# hand_pcb.net
KiCad netlist of a schematic drawn in EAGLE
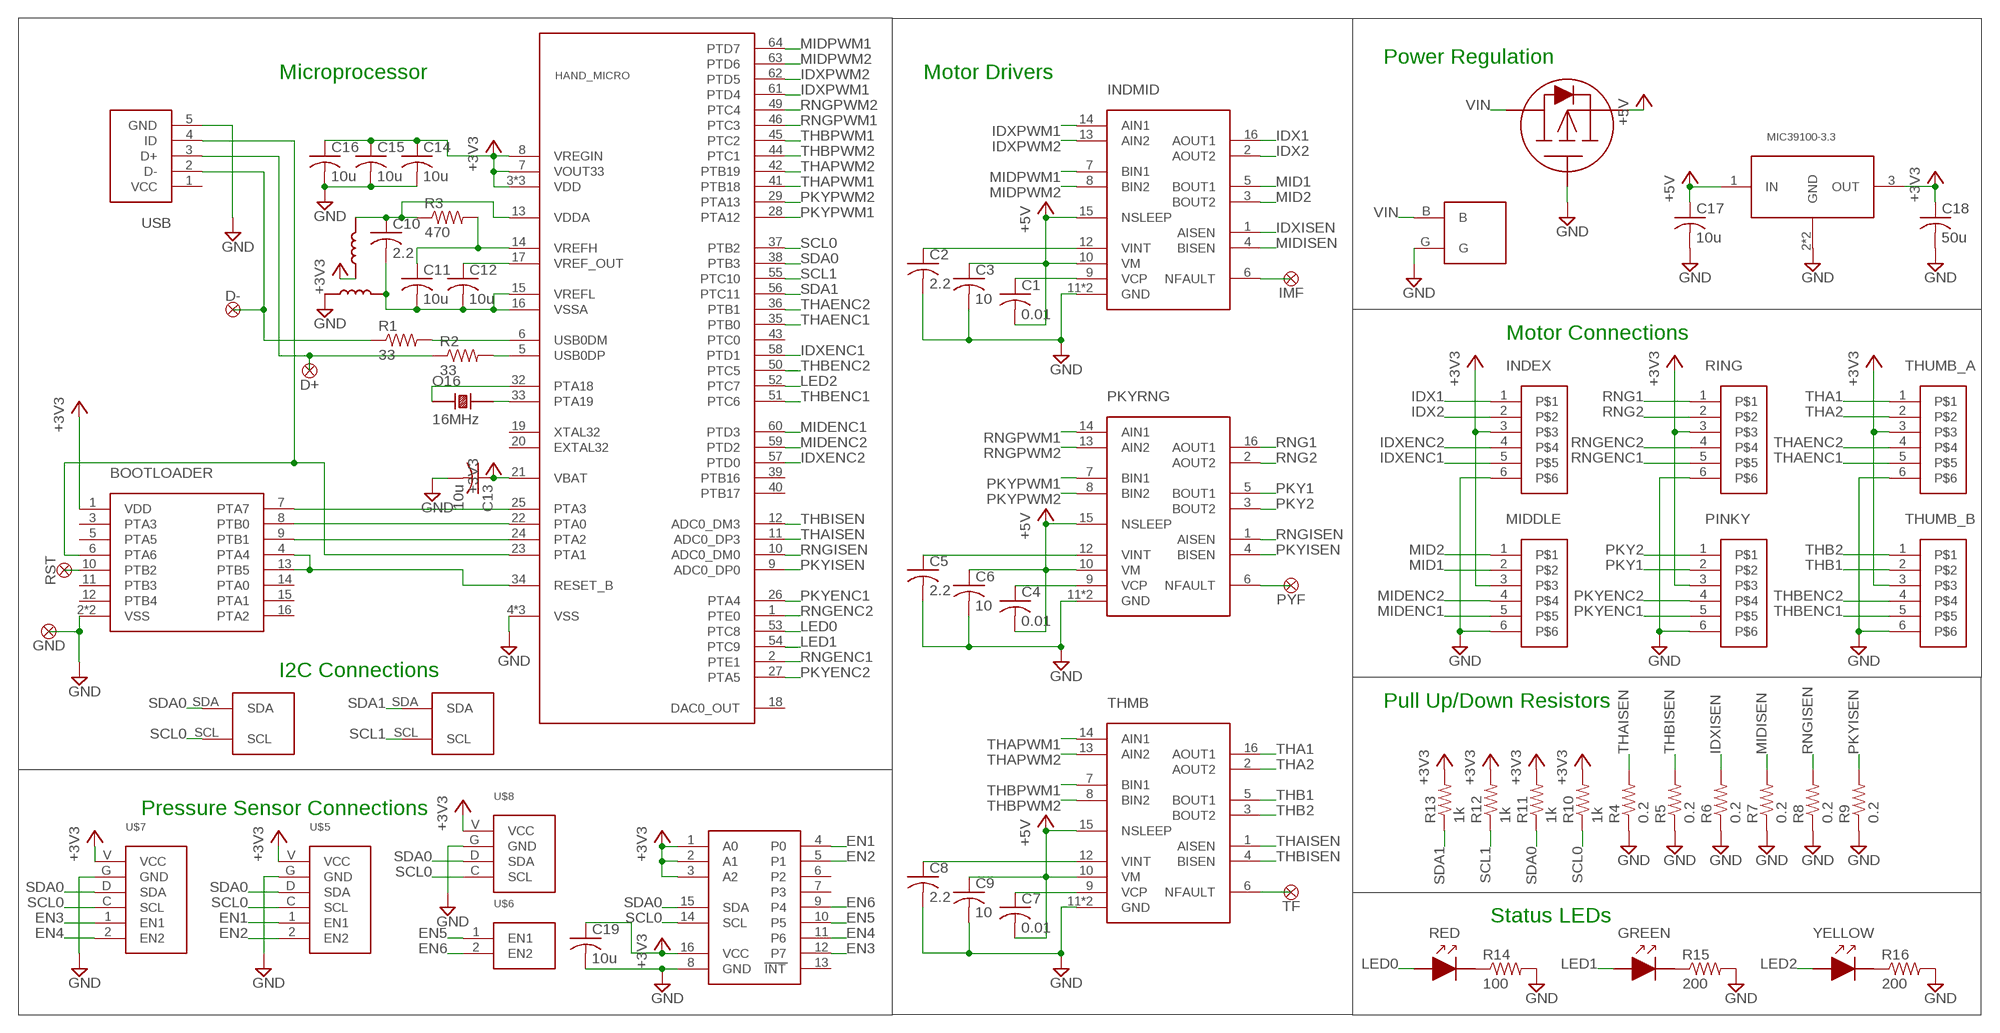
[diagram p0: schematic, sheet 1]

(export (version "E")
  (design (tool "Eeschema 10.0.6"))
  (components
    (comp (ref "BOOTLOADER")
      (value "MKL02Z32CORRECT")
      (footprint "eagle-import:QFN16")
      (libsource (lib "eagle-import") (part "MKL02Z32CORRECT"))
    )
    (comp (ref "C1")
      (value "0.01")
      (footprint "eagle-import:C0603")
      (libsource (lib "eagle-import") (part "C-USC0603"))
    )
    (comp (ref "C2")
      (value "2.2")
      (footprint "eagle-import:C0603")
      (libsource (lib "eagle-import") (part "C-USC0603"))
    )
    (comp (ref "C3")
      (value "10")
      (footprint "eagle-import:C0603")
      (libsource (lib "eagle-import") (part "C-USC0603"))
    )
    (comp (ref "C4")
      (value "0.01")
      (footprint "eagle-import:C0603")
      (libsource (lib "eagle-import") (part "C-USC0603"))
    )
    (comp (ref "C5")
      (value "2.2")
      (footprint "eagle-import:C0603")
      (libsource (lib "eagle-import") (part "C-USC0603"))
    )
    (comp (ref "C6")
      (value "10")
      (footprint "eagle-import:C0603")
      (libsource (lib "eagle-import") (part "C-USC0603"))
    )
    (comp (ref "C7")
      (value "0.01")
      (footprint "eagle-import:C0603")
      (libsource (lib "eagle-import") (part "C-USC0603"))
    )
    (comp (ref "C8")
      (value "2.2")
      (footprint "eagle-import:C0603")
      (libsource (lib "eagle-import") (part "C-USC0603"))
    )
    (comp (ref "C9")
      (value "10")
      (footprint "eagle-import:C0603")
      (libsource (lib "eagle-import") (part "C-USC0603"))
    )
    (comp (ref "C10")
      (value "2.2")
      (footprint "eagle-import:C0402")
      (libsource (lib "eagle-import") (part "C-USC0402"))
    )
    (comp (ref "C11")
      (value "10u")
      (footprint "eagle-import:C0402")
      (libsource (lib "eagle-import") (part "C-USC0402"))
    )
    (comp (ref "C12")
      (value "10u")
      (footprint "eagle-import:C0402")
      (libsource (lib "eagle-import") (part "C-USC0402"))
    )
    (comp (ref "C13")
      (value "10u")
      (footprint "eagle-import:C0402")
      (libsource (lib "eagle-import") (part "C-USC0402"))
    )
    (comp (ref "C14")
      (value "10u")
      (footprint "eagle-import:C0402")
      (libsource (lib "eagle-import") (part "C-USC0402"))
    )
    (comp (ref "C15")
      (value "10u")
      (footprint "eagle-import:C0402")
      (libsource (lib "eagle-import") (part "C-USC0402"))
    )
    (comp (ref "C16")
      (value "10u")
      (footprint "eagle-import:C0402")
      (libsource (lib "eagle-import") (part "C-USC0402"))
    )
    (comp (ref "C17")
      (value "10u")
      (footprint "eagle-import:C0603")
      (libsource (lib "eagle-import") (part "C-USC0603"))
    )
    (comp (ref "C18")
      (value "50u")
      (footprint "eagle-import:C0603")
      (libsource (lib "eagle-import") (part "C-USC0603"))
    )
    (comp (ref "C19")
      (value "10u")
      (footprint "eagle-import:C0402")
      (libsource (lib "eagle-import") (part "C-USC0402"))
    )
    (comp (ref "D+")
      (value "TESTPAD")
      (footprint "eagle-import:TESTPAD")
      (libsource (lib "eagle-import") (part "TESTPAD"))
    )
    (comp (ref "D-")
      (value "TESTPAD")
      (footprint "eagle-import:TESTPAD")
      (libsource (lib "eagle-import") (part "TESTPAD"))
    )
    (comp (ref "GND")
      (value "TESTPAD")
      (footprint "eagle-import:TESTPAD")
      (libsource (lib "eagle-import") (part "TESTPAD"))
    )
    (comp (ref "GREEN")
      (value "LED0603")
      (footprint "eagle-import:L0603")
      (libsource (lib "eagle-import") (part "LED0603"))
    )
    (comp (ref "HAND_MICRO")
      (value "MK20DX256VLH7")
      (footprint "eagle-import:LQFP-64-10-10")
      (libsource (lib "eagle-import") (part "MK20DX256VLH7"))
    )
    (comp (ref "IMF")
      (value "TESTPAD")
      (footprint "eagle-import:TESTPAD")
      (libsource (lib "eagle-import") (part "TESTPAD"))
    )
    (comp (ref "INDEX")
      (value "DF57H-6PTOP")
      (footprint "eagle-import:DF57H-6P-TOP")
      (libsource (lib "eagle-import") (part "DF57H-6PTOP"))
    )
    (comp (ref "INDMID")
      (value "DRV8833")
      (footprint "eagle-import:WQFN-16")
      (libsource (lib "eagle-import") (part "DRV8833"))
    )
    (comp (ref "MIDDLE")
      (value "DF57H-6PTOP")
      (footprint "eagle-import:DF57H-6P-TOP")
      (libsource (lib "eagle-import") (part "DF57H-6PTOP"))
    )
    (comp (ref "O16")
      (value "16MHz")
      (footprint "eagle-import:NX3225SA")
      (libsource (lib "eagle-import") (part "NX3225SA"))
    )
    (comp (ref "PINKY")
      (value "DF57H-6PTOP")
      (footprint "eagle-import:DF57H-6P-TOP")
      (libsource (lib "eagle-import") (part "DF57H-6PTOP"))
    )
    (comp (ref "PKYRNG")
      (value "DRV8833")
      (footprint "eagle-import:WQFN-16")
      (libsource (lib "eagle-import") (part "DRV8833"))
    )
    (comp (ref "PYF")
      (value "TESTPAD")
      (footprint "eagle-import:TESTPAD")
      (libsource (lib "eagle-import") (part "TESTPAD"))
    )
    (comp (ref "R1")
      (value "33")
      (footprint "eagle-import:R0402")
      (libsource (lib "eagle-import") (part "R-US_R0402"))
    )
    (comp (ref "R2")
      (value "33")
      (footprint "eagle-import:R0402")
      (libsource (lib "eagle-import") (part "R-US_R0402"))
    )
    (comp (ref "R3")
      (value "470")
      (footprint "eagle-import:R0402")
      (libsource (lib "eagle-import") (part "R-US_R0402"))
    )
    (comp (ref "R4")
      (value "0.2")
      (footprint "eagle-import:R1206")
      (libsource (lib "eagle-import") (part "R-US_R1206"))
    )
    (comp (ref "R5")
      (value "0.2")
      (footprint "eagle-import:R1206")
      (libsource (lib "eagle-import") (part "R-US_R1206"))
    )
    (comp (ref "R6")
      (value "0.2")
      (footprint "eagle-import:R1206")
      (libsource (lib "eagle-import") (part "R-US_R1206"))
    )
    (comp (ref "R7")
      (value "0.2")
      (footprint "eagle-import:R1206")
      (libsource (lib "eagle-import") (part "R-US_R1206"))
    )
    (comp (ref "R8")
      (value "0.2")
      (footprint "eagle-import:R1206")
      (libsource (lib "eagle-import") (part "R-US_R1206"))
    )
    (comp (ref "R9")
      (value "0.2")
      (footprint "eagle-import:R1206")
      (libsource (lib "eagle-import") (part "R-US_R1206"))
    )
    (comp (ref "R10")
      (value "1k")
      (footprint "eagle-import:R0603")
      (libsource (lib "eagle-import") (part "R-US_R0603"))
    )
    (comp (ref "R11")
      (value "1k")
      (footprint "eagle-import:R0603")
      (libsource (lib "eagle-import") (part "R-US_R0603"))
    )
    (comp (ref "R12")
      (value "1k")
      (footprint "eagle-import:R0603")
      (libsource (lib "eagle-import") (part "R-US_R0603"))
    )
    (comp (ref "R13")
      (value "1k")
      (footprint "eagle-import:R0603")
      (libsource (lib "eagle-import") (part "R-US_R0603"))
    )
    (comp (ref "R14")
      (value "100")
      (footprint "eagle-import:R0603")
      (libsource (lib "eagle-import") (part "R-US_R0603"))
    )
    (comp (ref "R15")
      (value "200")
      (footprint "eagle-import:R0603")
      (libsource (lib "eagle-import") (part "R-US_R0603"))
    )
    (comp (ref "R16")
      (value "200")
      (footprint "eagle-import:R0603")
      (libsource (lib "eagle-import") (part "R-US_R0603"))
    )
    (comp (ref "RED")
      (value "LED0603")
      (footprint "eagle-import:L0603")
      (libsource (lib "eagle-import") (part "LED0603"))
    )
    (comp (ref "RING")
      (value "DF57H-6PTOP")
      (footprint "eagle-import:DF57H-6P-TOP")
      (libsource (lib "eagle-import") (part "DF57H-6PTOP"))
    )
    (comp (ref "RST")
      (value "TESTPAD")
      (footprint "eagle-import:TESTPAD")
      (libsource (lib "eagle-import") (part "TESTPAD"))
    )
    (comp (ref "TF")
      (value "TESTPAD")
      (footprint "eagle-import:TESTPAD")
      (libsource (lib "eagle-import") (part "TESTPAD"))
    )
    (comp (ref "THMB")
      (value "DRV8833")
      (footprint "eagle-import:WQFN-16")
      (libsource (lib "eagle-import") (part "DRV8833"))
    )
    (comp (ref "THUMB_A")
      (value "DF57H-6PTOP")
      (footprint "eagle-import:DF57H-6P-TOP")
      (libsource (lib "eagle-import") (part "DF57H-6PTOP"))
    )
    (comp (ref "THUMB_B")
      (value "DF57H-6PTOP")
      (footprint "eagle-import:DF57H-6P-TOP")
      (libsource (lib "eagle-import") (part "DF57H-6PTOP"))
    )
    (comp (ref "U$1")
      (value "TCA9534TSSOP")
      (footprint "eagle-import:TSSOP16")
      (libsource (lib "eagle-import") (part "TCA9534TSSOP"))
    )
    (comp (ref "U$2")
      (value "SPD15P10PLG")
      (footprint "eagle-import:PG-TO-252-3")
      (libsource (lib "eagle-import") (part "SPD15P10PLG"))
    )
    (comp (ref "U$3")
      (value "FERRITE600OHM100MHZ")
      (footprint "eagle-import:L0603")
      (libsource (lib "eagle-import") (part "FERRITE600OHM100MHZ"))
    )
    (comp (ref "U$4")
      (value "FERRITE600OHM100MHZ")
      (footprint "eagle-import:L0603")
      (libsource (lib "eagle-import") (part "FERRITE600OHM100MHZ"))
    )
    (comp (ref "U$5")
      (value "PSENSE")
      (footprint "eagle-import:PSENSE")
      (libsource (lib "eagle-import") (part "PSENSE"))
    )
    (comp (ref "U$6")
      (value "PSENSE2")
      (footprint "eagle-import:PSENSE2")
      (libsource (lib "eagle-import") (part "PSENSE2"))
    )
    (comp (ref "U$7")
      (value "PSENSE")
      (footprint "eagle-import:PSENSE")
      (libsource (lib "eagle-import") (part "PSENSE"))
    )
    (comp (ref "U$8")
      (value "PSENSE4")
      (footprint "eagle-import:PSENSE4")
      (libsource (lib "eagle-import") (part "PSENSE4"))
    )
    (comp (ref "U$9")
      (value "MIC391003.3")
      (footprint "eagle-import:MIC39100")
      (libsource (lib "eagle-import") (part "MIC391003.3"))
    )
    (comp (ref "U$10")
      (value "THRUHOLE2")
      (footprint "eagle-import:THRUHOLE2")
      (libsource (lib "eagle-import") (part "THRUHOLE2"))
    )
    (comp (ref "U$11")
      (value "THRUHOLEI2C")
      (footprint "eagle-import:THRUHOLEI2C")
      (libsource (lib "eagle-import") (part "THRUHOLEI2C"))
    )
    (comp (ref "U$12")
      (value "THRUHOLEI2C")
      (footprint "eagle-import:THRUHOLEI2C")
      (libsource (lib "eagle-import") (part "THRUHOLEI2C"))
    )
    (comp (ref "USB")
      (value "10118194-0001LF")
      (footprint "eagle-import:10118194-0001LF")
      (libsource (lib "eagle-import") (part "10118194-0001LF"))
    )
    (comp (ref "YELLOW")
      (value "LED0603")
      (footprint "eagle-import:L0603")
      (libsource (lib "eagle-import") (part "LED0603"))
    )
  )
  (nets
    (net (code "1") (name "+3V3") (class "Default")
      (node (ref "BOOTLOADER") (pin "1") (pinfunction "VDD_1") (pintype "bidirectional"))
      (node (ref "C13") (pin "1") (pinfunction "1_1") (pintype "passive"))
      (node (ref "C14") (pin "1") (pinfunction "1_1") (pintype "passive"))
      (node (ref "C15") (pin "1") (pinfunction "1_1") (pintype "passive"))
      (node (ref "C16") (pin "1") (pinfunction "1_1") (pintype "passive"))
      (node (ref "C18") (pin "1") (pinfunction "1_1") (pintype "passive"))
      (node (ref "C19") (pin "1") (pinfunction "1_1") (pintype "passive"))
      (node (ref "HAND_MICRO") (pin "21") (pinfunction "VBAT_21") (pintype "bidirectional"))
      (node (ref "HAND_MICRO") (pin "3") (pinfunction "VDD_3") (pintype "bidirectional"))
      (node (ref "HAND_MICRO") (pin "30") (pinfunction "VDD_30") (pintype "bidirectional"))
      (node (ref "HAND_MICRO") (pin "48") (pinfunction "VDD_48") (pintype "bidirectional"))
      (node (ref "HAND_MICRO") (pin "7") (pinfunction "VOUT33_7") (pintype "bidirectional"))
      (node (ref "HAND_MICRO") (pin "8") (pinfunction "VREGIN_8") (pintype "bidirectional"))
      (node (ref "INDEX") (pin "3") (pinfunction "P$3_3") (pintype "bidirectional"))
      (node (ref "MIDDLE") (pin "3") (pinfunction "P$3_3") (pintype "bidirectional"))
      (node (ref "PINKY") (pin "3") (pinfunction "P$3_3") (pintype "bidirectional"))
      (node (ref "R10") (pin "2") (pinfunction "2_2") (pintype "passive"))
      (node (ref "R11") (pin "2") (pinfunction "2_2") (pintype "passive"))
      (node (ref "R12") (pin "2") (pinfunction "2_2") (pintype "passive"))
      (node (ref "R13") (pin "2") (pinfunction "2_2") (pintype "passive"))
      (node (ref "RING") (pin "3") (pinfunction "P$3_3") (pintype "bidirectional"))
      (node (ref "THUMB_A") (pin "3") (pinfunction "P$3_3") (pintype "bidirectional"))
      (node (ref "THUMB_B") (pin "3") (pinfunction "P$3_3") (pintype "bidirectional"))
      (node (ref "U$1") (pin "1") (pinfunction "A0_1") (pintype "bidirectional"))
      (node (ref "U$1") (pin "16") (pinfunction "VCC_16") (pintype "bidirectional"))
      (node (ref "U$1") (pin "2") (pinfunction "A1_2") (pintype "bidirectional"))
      (node (ref "U$1") (pin "3") (pinfunction "A2_3") (pintype "bidirectional"))
      (node (ref "U$4") (pin "1") (pinfunction "P$1_1") (pintype "bidirectional"))
      (node (ref "U$5") (pin "V") (pinfunction "VCC_V") (pintype "bidirectional"))
      (node (ref "U$7") (pin "V") (pinfunction "VCC_V") (pintype "bidirectional"))
      (node (ref "U$8") (pin "V") (pinfunction "VCC_V") (pintype "bidirectional"))
      (node (ref "U$9") (pin "3") (pinfunction "OUT_3") (pintype "bidirectional"))
    )
    (net (code "2") (name "+5V") (class "Default")
      (node (ref "C1") (pin "2") (pinfunction "2_2") (pintype "passive"))
      (node (ref "C17") (pin "1") (pinfunction "1_1") (pintype "passive"))
      (node (ref "C3") (pin "1") (pinfunction "1_1") (pintype "passive"))
      (node (ref "C4") (pin "2") (pinfunction "2_2") (pintype "passive"))
      (node (ref "C6") (pin "1") (pinfunction "1_1") (pintype "passive"))
      (node (ref "C7") (pin "2") (pinfunction "2_2") (pintype "passive"))
      (node (ref "C9") (pin "1") (pinfunction "1_1") (pintype "passive"))
      (node (ref "INDMID") (pin "10") (pinfunction "VM_10") (pintype "bidirectional"))
      (node (ref "INDMID") (pin "15") (pinfunction "NSLEEP_15") (pintype "bidirectional"))
      (node (ref "PKYRNG") (pin "10") (pinfunction "VM_10") (pintype "bidirectional"))
      (node (ref "PKYRNG") (pin "15") (pinfunction "NSLEEP_15") (pintype "bidirectional"))
      (node (ref "THMB") (pin "10") (pinfunction "VM_10") (pintype "bidirectional"))
      (node (ref "THMB") (pin "15") (pinfunction "NSLEEP_15") (pintype "bidirectional"))
      (node (ref "U$2") (pin "3") (pinfunction "3_3") (pintype "bidirectional"))
      (node (ref "U$9") (pin "1") (pinfunction "IN_1") (pintype "bidirectional"))
    )
    (net (code "3") (name "/EN1") (class "Default")
      (node (ref "U$1") (pin "4") (pinfunction "P0_4") (pintype "bidirectional"))
      (node (ref "U$5") (pin "1") (pinfunction "EN1_1") (pintype "bidirectional"))
    )
    (net (code "4") (name "/EN2") (class "Default")
      (node (ref "U$1") (pin "5") (pinfunction "P1_5") (pintype "bidirectional"))
      (node (ref "U$5") (pin "2") (pinfunction "EN2_2") (pintype "bidirectional"))
    )
    (net (code "5") (name "/EN3") (class "Default")
      (node (ref "U$1") (pin "12") (pinfunction "P7_12") (pintype "bidirectional"))
      (node (ref "U$7") (pin "1") (pinfunction "EN1_1") (pintype "bidirectional"))
    )
    (net (code "6") (name "/EN4") (class "Default")
      (node (ref "U$1") (pin "11") (pinfunction "P6_11") (pintype "bidirectional"))
      (node (ref "U$7") (pin "2") (pinfunction "EN2_2") (pintype "bidirectional"))
    )
    (net (code "7") (name "/EN5") (class "Default")
      (node (ref "U$1") (pin "10") (pinfunction "P5_10") (pintype "bidirectional"))
      (node (ref "U$6") (pin "1") (pinfunction "EN1_1") (pintype "bidirectional"))
    )
    (net (code "8") (name "/EN6") (class "Default")
      (node (ref "U$1") (pin "9") (pinfunction "P4_9") (pintype "bidirectional"))
      (node (ref "U$6") (pin "2") (pinfunction "EN2_2") (pintype "bidirectional"))
    )
    (net (code "9") (name "/IDX1") (class "Default")
      (node (ref "INDEX") (pin "1") (pinfunction "P$1_1") (pintype "bidirectional"))
      (node (ref "INDMID") (pin "16") (pinfunction "AOUT1_16") (pintype "bidirectional"))
    )
    (net (code "10") (name "/IDX2") (class "Default")
      (node (ref "INDEX") (pin "2") (pinfunction "P$2_2") (pintype "bidirectional"))
      (node (ref "INDMID") (pin "2") (pinfunction "AOUT2_2") (pintype "bidirectional"))
    )
    (net (code "11") (name "/IDXENC1") (class "Default")
      (node (ref "HAND_MICRO") (pin "58") (pinfunction "PTD1_58") (pintype "bidirectional"))
      (node (ref "INDEX") (pin "5") (pinfunction "P$5_5") (pintype "bidirectional"))
    )
    (net (code "12") (name "/IDXENC2") (class "Default")
      (node (ref "HAND_MICRO") (pin "57") (pinfunction "PTD0_57") (pintype "bidirectional"))
      (node (ref "INDEX") (pin "4") (pinfunction "P$4_4") (pintype "bidirectional"))
    )
    (net (code "13") (name "/IDXISEN") (class "Default")
      (node (ref "INDMID") (pin "1") (pinfunction "AISEN_1") (pintype "bidirectional"))
      (node (ref "R6") (pin "2") (pinfunction "2_2") (pintype "passive"))
    )
    (net (code "14") (name "/IDXPWM1") (class "Default")
      (node (ref "HAND_MICRO") (pin "61") (pinfunction "PTD4_61") (pintype "bidirectional"))
      (node (ref "INDMID") (pin "14") (pinfunction "AIN1_14") (pintype "bidirectional"))
    )
    (net (code "15") (name "/IDXPWM2") (class "Default")
      (node (ref "HAND_MICRO") (pin "62") (pinfunction "PTD5_62") (pintype "bidirectional"))
      (node (ref "INDMID") (pin "13") (pinfunction "AIN2_13") (pintype "bidirectional"))
    )
    (net (code "16") (name "/LED0") (class "Default")
      (node (ref "HAND_MICRO") (pin "53") (pinfunction "PTC8_53") (pintype "bidirectional"))
      (node (ref "RED") (pin "1") (pinfunction "P$1_1") (pintype "bidirectional"))
    )
    (net (code "17") (name "/LED1") (class "Default")
      (node (ref "GREEN") (pin "1") (pinfunction "P$1_1") (pintype "bidirectional"))
      (node (ref "HAND_MICRO") (pin "54") (pinfunction "PTC9_54") (pintype "bidirectional"))
    )
    (net (code "18") (name "/LED2") (class "Default")
      (node (ref "HAND_MICRO") (pin "52") (pinfunction "PTC7_52") (pintype "bidirectional"))
      (node (ref "YELLOW") (pin "1") (pinfunction "P$1_1") (pintype "bidirectional"))
    )
    (net (code "19") (name "/MID1") (class "Default")
      (node (ref "INDMID") (pin "5") (pinfunction "BOUT1_5") (pintype "bidirectional"))
      (node (ref "MIDDLE") (pin "2") (pinfunction "P$2_2") (pintype "bidirectional"))
    )
    (net (code "20") (name "/MID2") (class "Default")
      (node (ref "INDMID") (pin "3") (pinfunction "BOUT2_3") (pintype "bidirectional"))
      (node (ref "MIDDLE") (pin "1") (pinfunction "P$1_1") (pintype "bidirectional"))
    )
    (net (code "21") (name "/MIDENC1") (class "Default")
      (node (ref "HAND_MICRO") (pin "60") (pinfunction "PTD3_60") (pintype "bidirectional"))
      (node (ref "MIDDLE") (pin "5") (pinfunction "P$5_5") (pintype "bidirectional"))
    )
    (net (code "22") (name "/MIDENC2") (class "Default")
      (node (ref "HAND_MICRO") (pin "59") (pinfunction "PTD2_59") (pintype "bidirectional"))
      (node (ref "MIDDLE") (pin "4") (pinfunction "P$4_4") (pintype "bidirectional"))
    )
    (net (code "23") (name "/MIDISEN") (class "Default")
      (node (ref "INDMID") (pin "4") (pinfunction "BISEN_4") (pintype "bidirectional"))
      (node (ref "R7") (pin "2") (pinfunction "2_2") (pintype "passive"))
    )
    (net (code "24") (name "/MIDPWM1") (class "Default")
      (node (ref "HAND_MICRO") (pin "64") (pinfunction "PTD7_64") (pintype "bidirectional"))
      (node (ref "INDMID") (pin "7") (pinfunction "BIN1_7") (pintype "bidirectional"))
    )
    (net (code "25") (name "/MIDPWM2") (class "Default")
      (node (ref "HAND_MICRO") (pin "63") (pinfunction "PTD6_63") (pintype "bidirectional"))
      (node (ref "INDMID") (pin "8") (pinfunction "BIN2_8") (pintype "bidirectional"))
    )
    (net (code "26") (name "/PKY1") (class "Default")
      (node (ref "PINKY") (pin "2") (pinfunction "P$2_2") (pintype "bidirectional"))
      (node (ref "PKYRNG") (pin "5") (pinfunction "BOUT1_5") (pintype "bidirectional"))
    )
    (net (code "27") (name "/PKY2") (class "Default")
      (node (ref "PINKY") (pin "1") (pinfunction "P$1_1") (pintype "bidirectional"))
      (node (ref "PKYRNG") (pin "3") (pinfunction "BOUT2_3") (pintype "bidirectional"))
    )
    (net (code "28") (name "/PKYENC1") (class "Default")
      (node (ref "HAND_MICRO") (pin "26") (pinfunction "PTA4_26") (pintype "bidirectional"))
      (node (ref "PINKY") (pin "5") (pinfunction "P$5_5") (pintype "bidirectional"))
    )
    (net (code "29") (name "/PKYENC2") (class "Default")
      (node (ref "HAND_MICRO") (pin "27") (pinfunction "PTA5_27") (pintype "bidirectional"))
      (node (ref "PINKY") (pin "4") (pinfunction "P$4_4") (pintype "bidirectional"))
    )
    (net (code "30") (name "/PKYISEN") (class "Default")
      (node (ref "HAND_MICRO") (pin "9") (pinfunction "ADC0_DP0_9") (pintype "bidirectional"))
      (node (ref "PKYRNG") (pin "4") (pinfunction "BISEN_4") (pintype "bidirectional"))
      (node (ref "R9") (pin "2") (pinfunction "2_2") (pintype "passive"))
    )
    (net (code "31") (name "/PKYPWM1") (class "Default")
      (node (ref "HAND_MICRO") (pin "28") (pinfunction "PTA12_28") (pintype "bidirectional"))
      (node (ref "PKYRNG") (pin "7") (pinfunction "BIN1_7") (pintype "bidirectional"))
    )
    (net (code "32") (name "/PKYPWM2") (class "Default")
      (node (ref "HAND_MICRO") (pin "29") (pinfunction "PTA13_29") (pintype "bidirectional"))
      (node (ref "PKYRNG") (pin "8") (pinfunction "BIN2_8") (pintype "bidirectional"))
    )
    (net (code "33") (name "/RNG1") (class "Default")
      (node (ref "PKYRNG") (pin "16") (pinfunction "AOUT1_16") (pintype "bidirectional"))
      (node (ref "RING") (pin "1") (pinfunction "P$1_1") (pintype "bidirectional"))
    )
    (net (code "34") (name "/RNG2") (class "Default")
      (node (ref "PKYRNG") (pin "2") (pinfunction "AOUT2_2") (pintype "bidirectional"))
      (node (ref "RING") (pin "2") (pinfunction "P$2_2") (pintype "bidirectional"))
    )
    (net (code "35") (name "/RNGENC1") (class "Default")
      (node (ref "HAND_MICRO") (pin "2") (pinfunction "PTE1_2") (pintype "bidirectional"))
      (node (ref "RING") (pin "5") (pinfunction "P$5_5") (pintype "bidirectional"))
    )
    (net (code "36") (name "/RNGENC2") (class "Default")
      (node (ref "HAND_MICRO") (pin "1") (pinfunction "PTE0_1") (pintype "bidirectional"))
      (node (ref "RING") (pin "4") (pinfunction "P$4_4") (pintype "bidirectional"))
    )
    (net (code "37") (name "/RNGISEN") (class "Default")
      (node (ref "HAND_MICRO") (pin "10") (pinfunction "ADC0_DM0_10") (pintype "bidirectional"))
      (node (ref "PKYRNG") (pin "1") (pinfunction "AISEN_1") (pintype "bidirectional"))
      (node (ref "R8") (pin "2") (pinfunction "2_2") (pintype "passive"))
    )
    (net (code "38") (name "/RNGPWM1") (class "Default")
      (node (ref "HAND_MICRO") (pin "46") (pinfunction "PTC3_46") (pintype "bidirectional"))
      (node (ref "PKYRNG") (pin "14") (pinfunction "AIN1_14") (pintype "bidirectional"))
    )
    (net (code "39") (name "/RNGPWM2") (class "Default")
      (node (ref "HAND_MICRO") (pin "49") (pinfunction "PTC4_49") (pintype "bidirectional"))
      (node (ref "PKYRNG") (pin "13") (pinfunction "AIN2_13") (pintype "bidirectional"))
    )
    (net (code "40") (name "/SCL0") (class "Default")
      (node (ref "HAND_MICRO") (pin "37") (pinfunction "PTB2_37") (pintype "bidirectional"))
      (node (ref "R10") (pin "1") (pinfunction "1_1") (pintype "passive"))
      (node (ref "U$1") (pin "14") (pinfunction "SCL_14") (pintype "bidirectional"))
      (node (ref "U$11") (pin "SCL") (pinfunction "SCL_SCL") (pintype "bidirectional"))
      (node (ref "U$5") (pin "C") (pinfunction "SCL_C") (pintype "bidirectional"))
      (node (ref "U$7") (pin "C") (pinfunction "SCL_C") (pintype "bidirectional"))
      (node (ref "U$8") (pin "C") (pinfunction "SCL_C") (pintype "bidirectional"))
    )
    (net (code "41") (name "/SCL1") (class "Default")
      (node (ref "HAND_MICRO") (pin "55") (pinfunction "PTC10_55") (pintype "bidirectional"))
      (node (ref "R12") (pin "1") (pinfunction "1_1") (pintype "passive"))
      (node (ref "U$12") (pin "SCL") (pinfunction "SCL_SCL") (pintype "bidirectional"))
    )
    (net (code "42") (name "/SDA0") (class "Default")
      (node (ref "HAND_MICRO") (pin "38") (pinfunction "PTB3_38") (pintype "bidirectional"))
      (node (ref "R11") (pin "1") (pinfunction "1_1") (pintype "passive"))
      (node (ref "U$1") (pin "15") (pinfunction "SDA_15") (pintype "bidirectional"))
      (node (ref "U$11") (pin "SDA") (pinfunction "SDA_SDA") (pintype "bidirectional"))
      (node (ref "U$5") (pin "D") (pinfunction "SDA_D") (pintype "bidirectional"))
      (node (ref "U$7") (pin "D") (pinfunction "SDA_D") (pintype "bidirectional"))
      (node (ref "U$8") (pin "D") (pinfunction "SDA_D") (pintype "bidirectional"))
    )
    (net (code "43") (name "/SDA1") (class "Default")
      (node (ref "HAND_MICRO") (pin "56") (pinfunction "PTC11_56") (pintype "bidirectional"))
      (node (ref "R13") (pin "1") (pinfunction "1_1") (pintype "passive"))
      (node (ref "U$12") (pin "SDA") (pinfunction "SDA_SDA") (pintype "bidirectional"))
    )
    (net (code "44") (name "/THA1") (class "Default")
      (node (ref "THMB") (pin "16") (pinfunction "AOUT1_16") (pintype "bidirectional"))
      (node (ref "THUMB_A") (pin "1") (pinfunction "P$1_1") (pintype "bidirectional"))
    )
    (net (code "45") (name "/THA2") (class "Default")
      (node (ref "THMB") (pin "2") (pinfunction "AOUT2_2") (pintype "bidirectional"))
      (node (ref "THUMB_A") (pin "2") (pinfunction "P$2_2") (pintype "bidirectional"))
    )
    (net (code "46") (name "/THAENC1") (class "Default")
      (node (ref "HAND_MICRO") (pin "35") (pinfunction "PTB0_35") (pintype "bidirectional"))
      (node (ref "THUMB_A") (pin "5") (pinfunction "P$5_5") (pintype "bidirectional"))
    )
    (net (code "47") (name "/THAENC2") (class "Default")
      (node (ref "HAND_MICRO") (pin "36") (pinfunction "PTB1_36") (pintype "bidirectional"))
      (node (ref "THUMB_A") (pin "4") (pinfunction "P$4_4") (pintype "bidirectional"))
    )
    (net (code "48") (name "/THAISEN") (class "Default")
      (node (ref "HAND_MICRO") (pin "11") (pinfunction "ADC0_DP3_11") (pintype "bidirectional"))
      (node (ref "R4") (pin "2") (pinfunction "2_2") (pintype "passive"))
      (node (ref "THMB") (pin "1") (pinfunction "AISEN_1") (pintype "bidirectional"))
    )
    (net (code "49") (name "/THAPWM1") (class "Default")
      (node (ref "HAND_MICRO") (pin "41") (pinfunction "PTB18_41") (pintype "bidirectional"))
      (node (ref "THMB") (pin "14") (pinfunction "AIN1_14") (pintype "bidirectional"))
    )
    (net (code "50") (name "/THAPWM2") (class "Default")
      (node (ref "HAND_MICRO") (pin "42") (pinfunction "PTB19_42") (pintype "bidirectional"))
      (node (ref "THMB") (pin "13") (pinfunction "AIN2_13") (pintype "bidirectional"))
    )
    (net (code "51") (name "/THB1") (class "Default")
      (node (ref "THMB") (pin "5") (pinfunction "BOUT1_5") (pintype "bidirectional"))
      (node (ref "THUMB_B") (pin "2") (pinfunction "P$2_2") (pintype "bidirectional"))
    )
    (net (code "52") (name "/THB2") (class "Default")
      (node (ref "THMB") (pin "3") (pinfunction "BOUT2_3") (pintype "bidirectional"))
      (node (ref "THUMB_B") (pin "1") (pinfunction "P$1_1") (pintype "bidirectional"))
    )
    (net (code "53") (name "/THBENC1") (class "Default")
      (node (ref "HAND_MICRO") (pin "51") (pinfunction "PTC6_51") (pintype "bidirectional"))
      (node (ref "THUMB_B") (pin "5") (pinfunction "P$5_5") (pintype "bidirectional"))
    )
    (net (code "54") (name "/THBENC2") (class "Default")
      (node (ref "HAND_MICRO") (pin "50") (pinfunction "PTC5_50") (pintype "bidirectional"))
      (node (ref "THUMB_B") (pin "4") (pinfunction "P$4_4") (pintype "bidirectional"))
    )
    (net (code "55") (name "/THBISEN") (class "Default")
      (node (ref "HAND_MICRO") (pin "12") (pinfunction "ADC0_DM3_12") (pintype "bidirectional"))
      (node (ref "R5") (pin "2") (pinfunction "2_2") (pintype "passive"))
      (node (ref "THMB") (pin "4") (pinfunction "BISEN_4") (pintype "bidirectional"))
    )
    (net (code "56") (name "/THBPWM1") (class "Default")
      (node (ref "HAND_MICRO") (pin "45") (pinfunction "PTC2_45") (pintype "bidirectional"))
      (node (ref "THMB") (pin "7") (pinfunction "BIN1_7") (pintype "bidirectional"))
    )
    (net (code "57") (name "/THBPWM2") (class "Default")
      (node (ref "HAND_MICRO") (pin "44") (pinfunction "PTC1_44") (pintype "bidirectional"))
      (node (ref "THMB") (pin "8") (pinfunction "BIN2_8") (pintype "bidirectional"))
    )
    (net (code "58") (name "/VIN") (class "Default")
      (node (ref "U$10") (pin "B") (pinfunction "B_B") (pintype "bidirectional"))
      (node (ref "U$2") (pin "2") (pinfunction "2_2") (pintype "bidirectional"))
    )
    (net (code "59") (name "GND") (class "Default")
      (node (ref "BOOTLOADER") (pin "2") (pinfunction "VSS_2") (pintype "bidirectional"))
      (node (ref "BOOTLOADER") (pin "TH") (pinfunction "VSS_TH") (pintype "bidirectional"))
      (node (ref "C13") (pin "2") (pinfunction "2_2") (pintype "passive"))
      (node (ref "C14") (pin "2") (pinfunction "2_2") (pintype "passive"))
      (node (ref "C15") (pin "2") (pinfunction "2_2") (pintype "passive"))
      (node (ref "C16") (pin "2") (pinfunction "2_2") (pintype "passive"))
      (node (ref "C17") (pin "2") (pinfunction "2_2") (pintype "passive"))
      (node (ref "C18") (pin "2") (pinfunction "2_2") (pintype "passive"))
      (node (ref "C19") (pin "2") (pinfunction "2_2") (pintype "passive"))
      (node (ref "C2") (pin "2") (pinfunction "2_2") (pintype "passive"))
      (node (ref "C3") (pin "2") (pinfunction "2_2") (pintype "passive"))
      (node (ref "C5") (pin "2") (pinfunction "2_2") (pintype "passive"))
      (node (ref "C6") (pin "2") (pinfunction "2_2") (pintype "passive"))
      (node (ref "C8") (pin "2") (pinfunction "2_2") (pintype "passive"))
      (node (ref "C9") (pin "2") (pinfunction "2_2") (pintype "passive"))
      (node (ref "GND") (pin "P$1") (pinfunction "P$1_P$1") (pintype "bidirectional"))
      (node (ref "HAND_MICRO") (pin "31") (pinfunction "VSS_31") (pintype "bidirectional"))
      (node (ref "HAND_MICRO") (pin "4") (pinfunction "VSS_4") (pintype "bidirectional"))
      (node (ref "HAND_MICRO") (pin "47") (pinfunction "VSS_47") (pintype "bidirectional"))
      (node (ref "INDEX") (pin "6") (pinfunction "P$6_6") (pintype "bidirectional"))
      (node (ref "INDMID") (pin "11") (pinfunction "GND_11") (pintype "bidirectional"))
      (node (ref "INDMID") (pin "PPAD") (pinfunction "GND_PPAD") (pintype "bidirectional"))
      (node (ref "MIDDLE") (pin "6") (pinfunction "P$6_6") (pintype "bidirectional"))
      (node (ref "PINKY") (pin "6") (pinfunction "P$6_6") (pintype "bidirectional"))
      (node (ref "PKYRNG") (pin "11") (pinfunction "GND_11") (pintype "bidirectional"))
      (node (ref "PKYRNG") (pin "PPAD") (pinfunction "GND_PPAD") (pintype "bidirectional"))
      (node (ref "R14") (pin "2") (pinfunction "2_2") (pintype "passive"))
      (node (ref "R15") (pin "2") (pinfunction "2_2") (pintype "passive"))
      (node (ref "R16") (pin "2") (pinfunction "2_2") (pintype "passive"))
      (node (ref "R4") (pin "1") (pinfunction "1_1") (pintype "passive"))
      (node (ref "R5") (pin "1") (pinfunction "1_1") (pintype "passive"))
      (node (ref "R6") (pin "1") (pinfunction "1_1") (pintype "passive"))
      (node (ref "R7") (pin "1") (pinfunction "1_1") (pintype "passive"))
      (node (ref "R8") (pin "1") (pinfunction "1_1") (pintype "passive"))
      (node (ref "R9") (pin "1") (pinfunction "1_1") (pintype "passive"))
      (node (ref "RING") (pin "6") (pinfunction "P$6_6") (pintype "bidirectional"))
      (node (ref "THMB") (pin "11") (pinfunction "GND_11") (pintype "bidirectional"))
      (node (ref "THMB") (pin "PPAD") (pinfunction "GND_PPAD") (pintype "bidirectional"))
      (node (ref "THUMB_A") (pin "6") (pinfunction "P$6_6") (pintype "bidirectional"))
      (node (ref "THUMB_B") (pin "6") (pinfunction "P$6_6") (pintype "bidirectional"))
      (node (ref "U$1") (pin "8") (pinfunction "GND_8") (pintype "bidirectional"))
      (node (ref "U$10") (pin "G") (pinfunction "G_G") (pintype "bidirectional"))
      (node (ref "U$2") (pin "1") (pinfunction "1_1") (pintype "bidirectional"))
      (node (ref "U$3") (pin "1") (pinfunction "P$1_1") (pintype "bidirectional"))
      (node (ref "U$5") (pin "G") (pinfunction "GND_G") (pintype "bidirectional"))
      (node (ref "U$7") (pin "G") (pinfunction "GND_G") (pintype "bidirectional"))
      (node (ref "U$8") (pin "G") (pinfunction "GND_G") (pintype "bidirectional"))
      (node (ref "U$9") (pin "2") (pinfunction "GND_2") (pintype "bidirectional"))
      (node (ref "U$9") (pin "TAB") (pinfunction "GND_TAB") (pintype "bidirectional"))
      (node (ref "USB") (pin "5") (pinfunction "GND_5") (pintype "bidirectional"))
    )
    (net (code "60") (name "Net-(BOOTLOADER-PTA4)") (class "Default")
      (node (ref "BOOTLOADER") (pin "13") (pinfunction "PTB5_13") (pintype "bidirectional"))
      (node (ref "BOOTLOADER") (pin "4") (pinfunction "PTA4_4") (pintype "bidirectional"))
      (node (ref "HAND_MICRO") (pin "34") (pinfunction "RESET_B_34") (pintype "bidirectional"))
    )
    (net (code "61") (name "Net-(BOOTLOADER-PTA6)") (class "Default")
      (node (ref "BOOTLOADER") (pin "6") (pinfunction "PTA6_6") (pintype "bidirectional"))
      (node (ref "HAND_MICRO") (pin "23") (pinfunction "PTA1_23") (pintype "bidirectional"))
      (node (ref "USB") (pin "4") (pinfunction "ID_4") (pintype "bidirectional"))
    )
    (net (code "62") (name "Net-(BOOTLOADER-PTA7)") (class "Default")
      (node (ref "BOOTLOADER") (pin "7") (pinfunction "PTA7_7") (pintype "bidirectional"))
      (node (ref "HAND_MICRO") (pin "25") (pinfunction "PTA3_25") (pintype "bidirectional"))
    )
    (net (code "63") (name "Net-(BOOTLOADER-PTB0)") (class "Default")
      (node (ref "BOOTLOADER") (pin "8") (pinfunction "PTB0_8") (pintype "bidirectional"))
      (node (ref "HAND_MICRO") (pin "22") (pinfunction "PTA0_22") (pintype "bidirectional"))
    )
    (net (code "64") (name "Net-(BOOTLOADER-PTB1)") (class "Default")
      (node (ref "BOOTLOADER") (pin "9") (pinfunction "PTB1_9") (pintype "bidirectional"))
      (node (ref "HAND_MICRO") (pin "24") (pinfunction "PTA2_24") (pintype "bidirectional"))
    )
    (net (code "65") (name "Net-(BOOTLOADER-PTB2)") (class "Default")
      (node (ref "BOOTLOADER") (pin "10") (pinfunction "PTB2_10") (pintype "bidirectional"))
      (node (ref "RST") (pin "P$1") (pinfunction "P$1_P$1") (pintype "bidirectional"))
    )
    (net (code "66") (name "Net-(GREEN-P$2)") (class "Default")
      (node (ref "GREEN") (pin "2") (pinfunction "P$2_2") (pintype "bidirectional"))
      (node (ref "R15") (pin "1") (pinfunction "1_1") (pintype "passive"))
    )
    (net (code "67") (name "Net-(HAND_MICRO-PTA18)") (class "Default")
      (node (ref "HAND_MICRO") (pin "32") (pinfunction "PTA18_32") (pintype "bidirectional"))
      (node (ref "O16") (pin "1") (pinfunction "P$1_1") (pintype "bidirectional"))
    )
    (net (code "68") (name "Net-(HAND_MICRO-PTA19)") (class "Default")
      (node (ref "HAND_MICRO") (pin "33") (pinfunction "PTA19_33") (pintype "bidirectional"))
      (node (ref "O16") (pin "3") (pinfunction "P$2_3") (pintype "bidirectional"))
    )
    (net (code "69") (name "Net-(HAND_MICRO-USB0DM)") (class "Default")
      (node (ref "HAND_MICRO") (pin "6") (pinfunction "USB0DM_6") (pintype "bidirectional"))
      (node (ref "R1") (pin "2") (pinfunction "2_2") (pintype "passive"))
    )
    (net (code "70") (name "Net-(HAND_MICRO-USB0DP)") (class "Default")
      (node (ref "HAND_MICRO") (pin "5") (pinfunction "USB0DP_5") (pintype "bidirectional"))
      (node (ref "R2") (pin "2") (pinfunction "2_2") (pintype "passive"))
    )
    (net (code "71") (name "Net-(HAND_MICRO-VDDA)") (class "Default")
      (node (ref "C10") (pin "1") (pinfunction "1_1") (pintype "passive"))
      (node (ref "HAND_MICRO") (pin "13") (pinfunction "VDDA_13") (pintype "bidirectional"))
      (node (ref "R3") (pin "1") (pinfunction "1_1") (pintype "passive"))
      (node (ref "U$4") (pin "2") (pinfunction "P$2_2") (pintype "bidirectional"))
    )
    (net (code "72") (name "Net-(HAND_MICRO-VREFH)") (class "Default")
      (node (ref "C11") (pin "1") (pinfunction "1_1") (pintype "passive"))
      (node (ref "HAND_MICRO") (pin "14") (pinfunction "VREFH_14") (pintype "bidirectional"))
      (node (ref "R3") (pin "2") (pinfunction "2_2") (pintype "passive"))
    )
    (net (code "73") (name "Net-(HAND_MICRO-VREFL)") (class "Default")
      (node (ref "C10") (pin "2") (pinfunction "2_2") (pintype "passive"))
      (node (ref "C11") (pin "2") (pinfunction "2_2") (pintype "passive"))
      (node (ref "C12") (pin "2") (pinfunction "2_2") (pintype "passive"))
      (node (ref "HAND_MICRO") (pin "15") (pinfunction "VREFL_15") (pintype "bidirectional"))
      (node (ref "HAND_MICRO") (pin "16") (pinfunction "VSSA_16") (pintype "bidirectional"))
      (node (ref "U$3") (pin "2") (pinfunction "P$2_2") (pintype "bidirectional"))
    )
    (net (code "74") (name "Net-(HAND_MICRO-VREF_OUT)") (class "Default")
      (node (ref "C12") (pin "1") (pinfunction "1_1") (pintype "passive"))
      (node (ref "HAND_MICRO") (pin "17") (pinfunction "VREF_OUT_17") (pintype "bidirectional"))
    )
    (net (code "75") (name "Net-(INDMID-NFAULT)") (class "Default")
      (node (ref "IMF") (pin "P$1") (pinfunction "P$1_P$1") (pintype "bidirectional"))
      (node (ref "INDMID") (pin "6") (pinfunction "NFAULT_6") (pintype "bidirectional"))
    )
    (net (code "76") (name "Net-(INDMID-VCP)") (class "Default")
      (node (ref "C1") (pin "1") (pinfunction "1_1") (pintype "passive"))
      (node (ref "INDMID") (pin "9") (pinfunction "VCP_9") (pintype "bidirectional"))
    )
    (net (code "77") (name "Net-(INDMID-VINT)") (class "Default")
      (node (ref "C2") (pin "1") (pinfunction "1_1") (pintype "passive"))
      (node (ref "INDMID") (pin "12") (pinfunction "VINT_12") (pintype "bidirectional"))
    )
    (net (code "78") (name "Net-(PKYRNG-NFAULT)") (class "Default")
      (node (ref "PKYRNG") (pin "6") (pinfunction "NFAULT_6") (pintype "bidirectional"))
      (node (ref "PYF") (pin "P$1") (pinfunction "P$1_P$1") (pintype "bidirectional"))
    )
    (net (code "79") (name "Net-(PKYRNG-VCP)") (class "Default")
      (node (ref "C4") (pin "1") (pinfunction "1_1") (pintype "passive"))
      (node (ref "PKYRNG") (pin "9") (pinfunction "VCP_9") (pintype "bidirectional"))
    )
    (net (code "80") (name "Net-(PKYRNG-VINT)") (class "Default")
      (node (ref "C5") (pin "1") (pinfunction "1_1") (pintype "passive"))
      (node (ref "PKYRNG") (pin "12") (pinfunction "VINT_12") (pintype "bidirectional"))
    )
    (net (code "81") (name "Net-(RED-P$2)") (class "Default")
      (node (ref "R14") (pin "1") (pinfunction "1_1") (pintype "passive"))
      (node (ref "RED") (pin "2") (pinfunction "P$2_2") (pintype "bidirectional"))
    )
    (net (code "82") (name "Net-(THMB-NFAULT)") (class "Default")
      (node (ref "TF") (pin "P$1") (pinfunction "P$1_P$1") (pintype "bidirectional"))
      (node (ref "THMB") (pin "6") (pinfunction "NFAULT_6") (pintype "bidirectional"))
    )
    (net (code "83") (name "Net-(THMB-VCP)") (class "Default")
      (node (ref "C7") (pin "1") (pinfunction "1_1") (pintype "passive"))
      (node (ref "THMB") (pin "9") (pinfunction "VCP_9") (pintype "bidirectional"))
    )
    (net (code "84") (name "Net-(THMB-VINT)") (class "Default")
      (node (ref "C8") (pin "1") (pinfunction "1_1") (pintype "passive"))
      (node (ref "THMB") (pin "12") (pinfunction "VINT_12") (pintype "bidirectional"))
    )
    (net (code "85") (name "Net-(USB-D+)") (class "Default")
      (node (ref "D+") (pin "P$1") (pinfunction "P$1_P$1") (pintype "bidirectional"))
      (node (ref "R2") (pin "1") (pinfunction "1_1") (pintype "passive"))
      (node (ref "USB") (pin "3") (pinfunction "D+_3") (pintype "bidirectional"))
    )
    (net (code "86") (name "Net-(USB-D-)") (class "Default")
      (node (ref "D-") (pin "P$1") (pinfunction "P$1_P$1") (pintype "bidirectional"))
      (node (ref "R1") (pin "1") (pinfunction "1_1") (pintype "passive"))
      (node (ref "USB") (pin "2") (pinfunction "D-_2") (pintype "bidirectional"))
    )
    (net (code "87") (name "Net-(YELLOW-P$2)") (class "Default")
      (node (ref "R16") (pin "1") (pinfunction "1_1") (pintype "passive"))
      (node (ref "YELLOW") (pin "2") (pinfunction "P$2_2") (pintype "bidirectional"))
    )
    (net (code "88") (name "unconnected-(BOOTLOADER-PTA0-Pad14)") (class "Default")
      (node (ref "BOOTLOADER") (pin "14") (pinfunction "PTA0_14") (pintype "bidirectional"))
    )
    (net (code "89") (name "unconnected-(BOOTLOADER-PTA1-Pad15)") (class "Default")
      (node (ref "BOOTLOADER") (pin "15") (pinfunction "PTA1_15") (pintype "bidirectional"))
    )
    (net (code "90") (name "unconnected-(BOOTLOADER-PTA2-Pad16)") (class "Default")
      (node (ref "BOOTLOADER") (pin "16") (pinfunction "PTA2_16") (pintype "bidirectional"))
    )
    (net (code "91") (name "unconnected-(BOOTLOADER-PTA3-Pad3)") (class "Default")
      (node (ref "BOOTLOADER") (pin "3") (pinfunction "PTA3_3") (pintype "bidirectional"))
    )
    (net (code "92") (name "unconnected-(BOOTLOADER-PTA5-Pad5)") (class "Default")
      (node (ref "BOOTLOADER") (pin "5") (pinfunction "PTA5_5") (pintype "bidirectional"))
    )
    (net (code "93") (name "unconnected-(BOOTLOADER-PTB3-Pad11)") (class "Default")
      (node (ref "BOOTLOADER") (pin "11") (pinfunction "PTB3_11") (pintype "bidirectional"))
    )
    (net (code "94") (name "unconnected-(BOOTLOADER-PTB4-Pad12)") (class "Default")
      (node (ref "BOOTLOADER") (pin "12") (pinfunction "PTB4_12") (pintype "bidirectional"))
    )
    (net (code "95") (name "unconnected-(HAND_MICRO-DAC0_OUT-Pad18)") (class "Default")
      (node (ref "HAND_MICRO") (pin "18") (pinfunction "DAC0_OUT_18") (pintype "bidirectional"))
    )
    (net (code "96") (name "unconnected-(HAND_MICRO-EXTAL32-Pad20)") (class "Default")
      (node (ref "HAND_MICRO") (pin "20") (pinfunction "EXTAL32_20") (pintype "bidirectional"))
    )
    (net (code "97") (name "unconnected-(HAND_MICRO-PTB16-Pad39)") (class "Default")
      (node (ref "HAND_MICRO") (pin "39") (pinfunction "PTB16_39") (pintype "bidirectional"))
    )
    (net (code "98") (name "unconnected-(HAND_MICRO-PTB17-Pad40)") (class "Default")
      (node (ref "HAND_MICRO") (pin "40") (pinfunction "PTB17_40") (pintype "bidirectional"))
    )
    (net (code "99") (name "unconnected-(HAND_MICRO-PTC0-Pad43)") (class "Default")
      (node (ref "HAND_MICRO") (pin "43") (pinfunction "PTC0_43") (pintype "bidirectional"))
    )
    (net (code "100") (name "unconnected-(HAND_MICRO-XTAL32-Pad19)") (class "Default")
      (node (ref "HAND_MICRO") (pin "19") (pinfunction "XTAL32_19") (pintype "bidirectional"))
    )
    (net (code "101") (name "unconnected-(U$1-INT-Pad13)") (class "Default")
      (node (ref "U$1") (pin "13") (pinfunction "INT_13") (pintype "bidirectional"))
    )
    (net (code "102") (name "unconnected-(U$1-P2-Pad6)") (class "Default")
      (node (ref "U$1") (pin "6") (pinfunction "P2_6") (pintype "bidirectional"))
    )
    (net (code "103") (name "unconnected-(U$1-P3-Pad7)") (class "Default")
      (node (ref "U$1") (pin "7") (pinfunction "P3_7") (pintype "bidirectional"))
    )
    (net (code "104") (name "unconnected-(USB-VCC-Pad1)") (class "Default")
      (node (ref "USB") (pin "1") (pinfunction "VCC_1") (pintype "bidirectional"))
    )
  )
)
